# source_A.net
KiCad netlist of a schematic drawn in Altium Designer
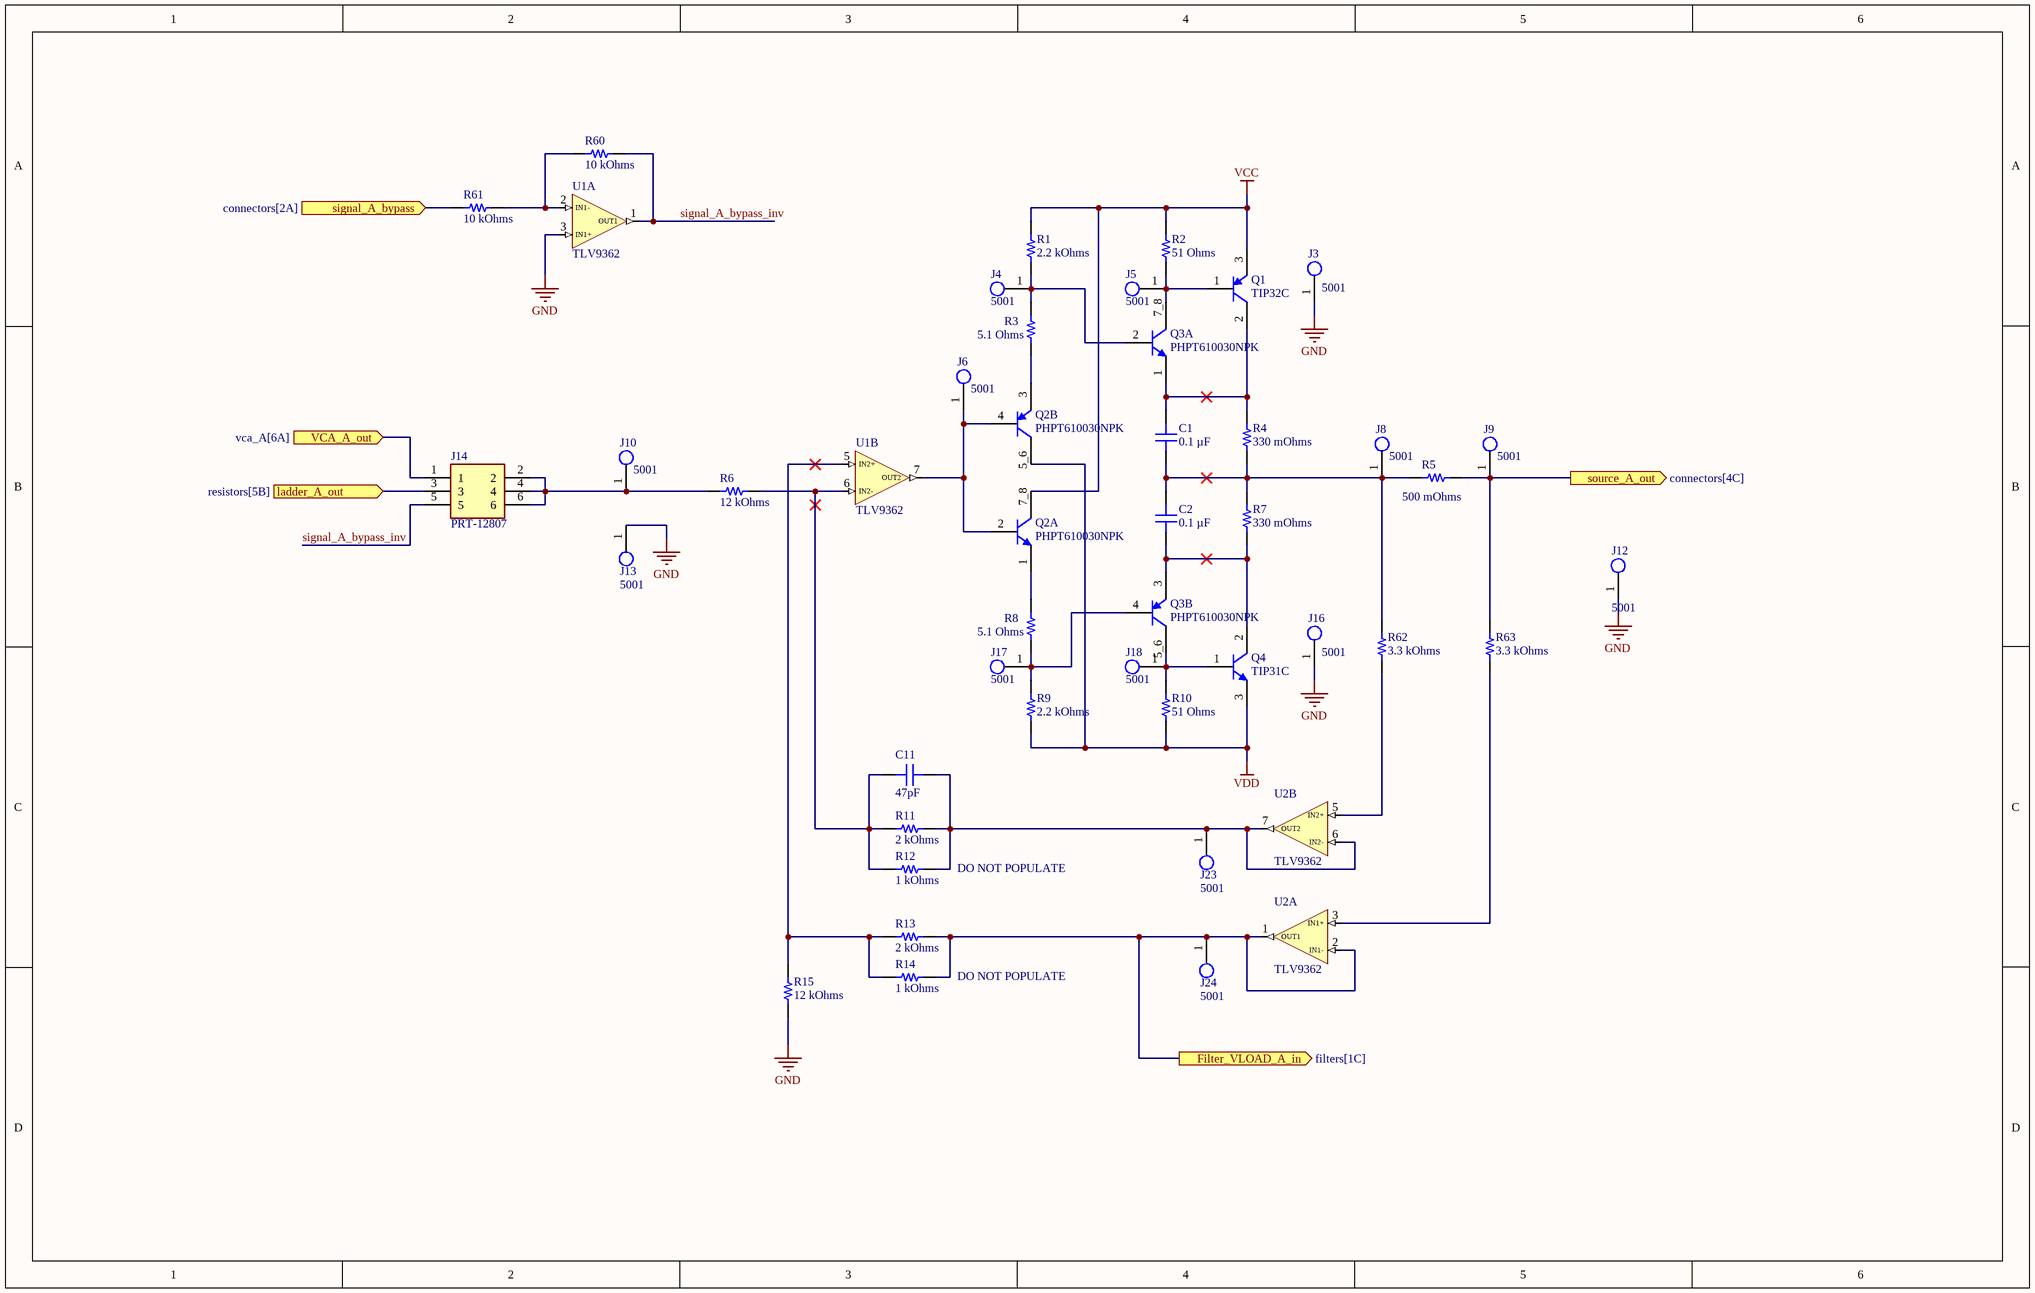
[diagram p0: source_A.SchDoc]

(export (version "E")
  (design (tool "Eeschema 10.0.6"))
  (components
    (comp (ref "C1")
      (value "0.1 µF")
      (footprint "CAP 1206_3216 - 0.8MM")
      (description "CAP CER 0.1UF 50V X7R 1206")
      (fields
        (field (name "PART NUMBER") "885012208087")
        (field (name "CAPACITANCE") "0.1 µF")
        (field (name "MANUFACTURER") "Würth Elektronik")
      )
      (libsource (lib "Celestial Altium Library - altium_library") (part "Capacitor"))
    )
    (comp (ref "C2")
      (value "0.1 µF")
      (footprint "CAP 1206_3216 - 0.8MM")
      (description "CAP CER 0.1UF 50V X7R 1206")
      (fields
        (field (name "PART NUMBER") "885012208087")
        (field (name "CAPACITANCE") "0.1 µF")
        (field (name "MANUFACTURER") "Würth Elektronik")
      )
      (libsource (lib "Celestial Altium Library - altium_library") (part "Capacitor"))
    )
    (comp (ref "C11")
      (value "47pF")
      (footprint "CAP 1206_3216 - 1.8MM")
      (description "CAP CER 47PF 1KV C0G/NP0 1206")
      (fields
        (field (name "PART NUMBER") "1206AA470KAT1A")
        (field (name "CAPACITANCE") "47pF")
        (field (name "MANUFACTURER") "AVX Corporation")
      )
      (libsource (lib "Celestial Altium Library - altium_library") (part "Capacitor"))
    )
    (comp (ref "J3")
      (value "5001")
      (footprint "FP-5001-MFG")
      (description "PC TEST POINT MINIATURE BLACK")
      (libsource (lib "za_koncar") (part "CMP-2000-05181-2"))
    )
    (comp (ref "J4")
      (value "5001")
      (footprint "FP-5001-MFG")
      (description "PC TEST POINT MINIATURE BLACK")
      (libsource (lib "za_koncar") (part "CMP-2000-05181-2"))
    )
    (comp (ref "J5")
      (value "5001")
      (footprint "FP-5001-MFG")
      (description "PC TEST POINT MINIATURE BLACK")
      (libsource (lib "za_koncar") (part "CMP-2000-05181-2"))
    )
    (comp (ref "J6")
      (value "5001")
      (footprint "FP-5001-MFG")
      (description "PC TEST POINT MINIATURE BLACK")
      (libsource (lib "za_koncar") (part "CMP-2000-05181-2"))
    )
    (comp (ref "J8")
      (value "5001")
      (footprint "FP-5001-MFG")
      (description "PC TEST POINT MINIATURE BLACK")
      (libsource (lib "za_koncar") (part "CMP-2000-05181-2"))
    )
    (comp (ref "J9")
      (value "5001")
      (footprint "FP-5001-MFG")
      (description "PC TEST POINT MINIATURE BLACK")
      (libsource (lib "za_koncar") (part "CMP-2000-05181-2"))
    )
    (comp (ref "J10")
      (value "5001")
      (footprint "FP-5001-MFG")
      (description "PC TEST POINT MINIATURE BLACK")
      (libsource (lib "za_koncar") (part "CMP-2000-05181-2"))
    )
    (comp (ref "J12")
      (value "5001")
      (footprint "FP-5001-MFG")
      (description "PC TEST POINT MINIATURE BLACK")
      (libsource (lib "za_koncar") (part "CMP-2000-05181-2"))
    )
    (comp (ref "J13")
      (value "5001")
      (footprint "FP-5001-MFG")
      (description "PC TEST POINT MINIATURE BLACK")
      (libsource (lib "za_koncar") (part "CMP-2000-05181-2"))
    )
    (comp (ref "J14")
      (value "PRT-12807")
      (footprint "HDRV6W82P254_2X3_762X500X884P")
      (description "Connector")
      (fields (field (name "MOUSER PART NUMBER") "474-PRT-12807"))
      (libsource (lib "za_koncar") (part "PRT-12807"))
    )
    (comp (ref "J16")
      (value "5001")
      (footprint "FP-5001-MFG")
      (description "PC TEST POINT MINIATURE BLACK")
      (libsource (lib "za_koncar") (part "CMP-2000-05181-2"))
    )
    (comp (ref "J17")
      (value "5001")
      (footprint "FP-5001-MFG")
      (description "PC TEST POINT MINIATURE BLACK")
      (libsource (lib "za_koncar") (part "CMP-2000-05181-2"))
    )
    (comp (ref "J18")
      (value "5001")
      (footprint "FP-5001-MFG")
      (description "PC TEST POINT MINIATURE BLACK")
      (libsource (lib "za_koncar") (part "CMP-2000-05181-2"))
    )
    (comp (ref "J23")
      (value "5001")
      (footprint "FP-5001-MFG")
      (description "PC TEST POINT MINIATURE BLACK")
      (libsource (lib "za_koncar") (part "CMP-2000-05181-2"))
    )
    (comp (ref "J24")
      (value "5001")
      (footprint "FP-5001-MFG")
      (description "PC TEST POINT MINIATURE BLACK")
      (libsource (lib "za_koncar") (part "CMP-2000-05181-2"))
    )
    (comp (ref "Q1")
      (value "TIP32C")
      (footprint "ONSC-TO-220-3-221A-09")
      (description "Complementary Silicon Plastic Power Transistor, 3-Pin TO-220, Tube")
      (fields (field (name "MANUFACTURER") "On Semiconductor"))
      (libsource (lib "ON Semi General Purpose Transistors") (part "TIP32C"))
    )
    (comp (ref "Q2")
      (value "PHPT610030NPK")
      (footprint "TRANS_BUK9K18-40E,115")
      (libsource (lib "za_koncar") (part "PHPT610030NPK"))
    )
    (comp (ref "Q3")
      (value "PHPT610030NPK")
      (footprint "TRANS_BUK9K18-40E,115")
      (libsource (lib "za_koncar") (part "PHPT610030NPK"))
    )
    (comp (ref "Q4")
      (value "TIP31C")
      (footprint "ONSC-TO-220-3-221A-09")
      (description "Complementary Silicon Plastic Power Transistor, 3-Pin TO-220, Tube")
      (fields (field (name "MANUFACTURER") "On Semiconductor"))
      (libsource (lib "ON Semi General Purpose Transistors") (part "TIP31C"))
    )
    (comp (ref "R1")
      (value "2.2 kOhms")
      (footprint "RES 1206_3216")
      (description "RES SMD 2.2K OHM 5% 1/4W 1206")
      (fields
        (field (name "PART NUMBER") "ERJ-8GEYJ222V")
        (field (name "MANUFACTURER") "Panasonic Electronic Components")
      )
      (libsource (lib "Celestial Altium Library - altium_library") (part "Resistor"))
    )
    (comp (ref "R2")
      (value "51 Ohms")
      (footprint "RES 1206_3216")
      (description "RES SMD 51 OHM 5% 1/4W 1206")
      (fields
        (field (name "PART NUMBER") "ERJ-8GEYJ510V")
        (field (name "MANUFACTURER") "Panasonic Electronic Components")
      )
      (libsource (lib "Celestial Altium Library - altium_library") (part "Resistor"))
    )
    (comp (ref "R3")
      (value "5.1 Ohms")
      (footprint "RES 1206_3216")
      (description "RES SMD 5.1 OHM 5% 1/4W 1206")
      (fields
        (field (name "PART NUMBER") "ERJ-8GEYJ5R1V")
        (field (name "MANUFACTURER") "Panasonic Electronic Components")
      )
      (libsource (lib "Celestial Altium Library - altium_library") (part "Resistor"))
    )
    (comp (ref "R4")
      (value "330 mOhms")
      (footprint "STACKPOLE CSR2512")
      (description "RES 0.33 OHM 1% 2W 2512")
      (fields
        (field (name "PART NUMBER") "CSRN2512FKR330")
        (field (name "MANUFACTURER") "Stackpole Electronics Inc")
      )
      (libsource (lib "Celestial Altium Library - altium_library") (part "Resistor"))
    )
    (comp (ref "R5")
      (value "500 mOhms")
      (footprint "STACKPOLE CSR2512")
      (description "RES 0.5 OHM 1% 2W 2512")
      (fields
        (field (name "PART NUMBER") "CSRN2512FKR500")
        (field (name "MANUFACTURER") "Stackpole Electronics Inc")
      )
      (libsource (lib "Celestial Altium Library - altium_library") (part "Resistor"))
    )
    (comp (ref "R6")
      (value "12 kOhms")
      (footprint "RES 1206_3216")
      (description "RES SMD 12K OHM 0.1% 1/4W 1206")
      (fields
        (field (name "PART NUMBER") "ERA-8AEB123V")
        (field (name "MANUFACTURER") "Panasonic Electronic Components")
      )
      (libsource (lib "Celestial Altium Library - altium_library") (part "Resistor"))
    )
    (comp (ref "R7")
      (value "330 mOhms")
      (footprint "STACKPOLE CSR2512")
      (description "RES 0.33 OHM 1% 2W 2512")
      (fields
        (field (name "PART NUMBER") "CSRN2512FKR330")
        (field (name "MANUFACTURER") "Stackpole Electronics Inc")
      )
      (libsource (lib "Celestial Altium Library - altium_library") (part "Resistor"))
    )
    (comp (ref "R8")
      (value "5.1 Ohms")
      (footprint "RES 1206_3216")
      (description "RES SMD 5.1 OHM 5% 1/4W 1206")
      (fields
        (field (name "PART NUMBER") "ERJ-8GEYJ5R1V")
        (field (name "MANUFACTURER") "Panasonic Electronic Components")
      )
      (libsource (lib "Celestial Altium Library - altium_library") (part "Resistor"))
    )
    (comp (ref "R9")
      (value "2.2 kOhms")
      (footprint "RES 1206_3216")
      (description "RES SMD 2.2K OHM 5% 1/4W 1206")
      (fields
        (field (name "PART NUMBER") "ERJ-8GEYJ222V")
        (field (name "MANUFACTURER") "Panasonic Electronic Components")
      )
      (libsource (lib "Celestial Altium Library - altium_library") (part "Resistor"))
    )
    (comp (ref "R10")
      (value "51 Ohms")
      (footprint "RES 1206_3216")
      (description "RES SMD 51 OHM 5% 1/4W 1206")
      (fields
        (field (name "PART NUMBER") "ERJ-8GEYJ510V")
        (field (name "MANUFACTURER") "Panasonic Electronic Components")
      )
      (libsource (lib "Celestial Altium Library - altium_library") (part "Resistor"))
    )
    (comp (ref "R11")
      (value "2 kOhms")
      (footprint "RES 1206_3216")
      (description "RES SMD 2K OHM 0.1% 1/4W 1206")
      (fields
        (field (name "PART NUMBER") "ERA-8AEB202V")
        (field (name "MANUFACTURER") "Panasonic Electronic Components")
      )
      (libsource (lib "Celestial Altium Library - altium_library") (part "Resistor"))
    )
    (comp (ref "R12")
      (value "1 kOhms")
      (footprint "RES 1206_3216")
      (description "RES SMD 1K OHM 0.1% 1/4W 1206")
      (fields
        (field (name "PART NUMBER") "ERA-8AEB102V")
        (field (name "MANUFACTURER") "Panasonic Electronic Components")
      )
      (libsource (lib "Celestial Altium Library - altium_library") (part "Resistor"))
    )
    (comp (ref "R13")
      (value "2 kOhms")
      (footprint "RES 1206_3216")
      (description "RES SMD 2K OHM 0.1% 1/4W 1206")
      (fields
        (field (name "PART NUMBER") "ERA-8AEB202V")
        (field (name "MANUFACTURER") "Panasonic Electronic Components")
      )
      (libsource (lib "Celestial Altium Library - altium_library") (part "Resistor"))
    )
    (comp (ref "R14")
      (value "1 kOhms")
      (footprint "RES 1206_3216")
      (description "RES SMD 1K OHM 0.1% 1/4W 1206")
      (fields
        (field (name "PART NUMBER") "ERA-8AEB102V")
        (field (name "MANUFACTURER") "Panasonic Electronic Components")
      )
      (libsource (lib "Celestial Altium Library - altium_library") (part "Resistor"))
    )
    (comp (ref "R15")
      (value "12 kOhms")
      (footprint "RES 1206_3216")
      (description "RES SMD 12K OHM 0.1% 1/4W 1206")
      (fields
        (field (name "PART NUMBER") "ERA-8AEB123V")
        (field (name "MANUFACTURER") "Panasonic Electronic Components")
      )
      (libsource (lib "Celestial Altium Library - altium_library") (part "Resistor"))
    )
    (comp (ref "R60")
      (value "10 kOhms")
      (footprint "YAGEO RES 1206_3216")
      (description "RES SMD 10K OHM 1% 1/4W 1206")
      (fields (field (name "PART NUMBER") "RT1206FRE0710KL") (field (name "MANUFACTURER") "Yageo"))
      (libsource (lib "Celestial Altium Library - altium_library") (part "Resistor"))
    )
    (comp (ref "R61")
      (value "10 kOhms")
      (footprint "YAGEO RES 1206_3216")
      (description "RES SMD 10K OHM 1% 1/4W 1206")
      (fields (field (name "PART NUMBER") "RT1206FRE0710KL") (field (name "MANUFACTURER") "Yageo"))
      (libsource (lib "Celestial Altium Library - altium_library") (part "Resistor"))
    )
    (comp (ref "R62")
      (value "3.3 kOhms")
      (footprint "YAGEO RES 1206_3216")
      (description "RES SMD 3.3K OHM 1% 1/4W 1206")
      (fields (field (name "PART NUMBER") "RT1206FRE073K3L") (field (name "MANUFACTURER") "Yageo"))
      (libsource (lib "Celestial Altium Library - altium_library") (part "Resistor"))
    )
    (comp (ref "R63")
      (value "3.3 kOhms")
      (footprint "YAGEO RES 1206_3216")
      (description "RES SMD 3.3K OHM 1% 1/4W 1206")
      (fields (field (name "PART NUMBER") "RT1206FRE073K3L") (field (name "MANUFACTURER") "Yageo"))
      (libsource (lib "Celestial Altium Library - altium_library") (part "Resistor"))
    )
    (comp (ref "U1")
      (value "TLV9362")
      (footprint "za_koncar:SOIC8-127P600X175-8N")
      (description "TLV936x 10-MHz, 40-V, RRO, Operational Amplifie")
      (libsource (lib "za_koncar") (part "TLV9362"))
    )
    (comp (ref "U2")
      (value "TLV9362")
      (footprint "za_koncar:SOIC8-127P600X175-8N")
      (description "TLV936x 10-MHz, 40-V, RRO, Operational Amplifie")
      (libsource (lib "za_koncar") (part "TLV9362"))
    )
  )
  (nets
    (net (code "1") (name "/Filter_VLOAD_A_in") (class "Default")
      (node (ref "J24") (pin "1") (pinfunction "1_1") (pintype "passive"))
      (node (ref "R13") (pin "2") (pinfunction "2_2") (pintype "passive"))
      (node (ref "R14") (pin "2") (pinfunction "2_2") (pintype "passive"))
      (node (ref "U2") (pin "1") (pinfunction "OUT1_1") (pintype "output"))
      (node (ref "U2") (pin "2") (pinfunction "IN1-_2") (pintype "input"))
    )
    (net (code "2") (name "/VCA_A_out") (class "Default")
      (node (ref "J14") (pin "1") (pinfunction "1_1") (pintype "passive"))
    )
    (net (code "3") (name "/ladder_A_out") (class "Default")
      (node (ref "J14") (pin "3") (pinfunction "3_3") (pintype "passive"))
    )
    (net (code "4") (name "/signal_A_bypass") (class "Default")
      (node (ref "R61") (pin "2") (pinfunction "2_2") (pintype "passive"))
    )
    (net (code "5") (name "/signal_A_bypass_inv") (class "Default")
      (node (ref "J14") (pin "5") (pinfunction "5_5") (pintype "passive"))
      (node (ref "R60") (pin "2") (pinfunction "2_2") (pintype "passive"))
      (node (ref "U1") (pin "1") (pinfunction "OUT1_1") (pintype "output"))
    )
    (net (code "6") (name "/source_A_out") (class "Default")
      (node (ref "J9") (pin "1") (pinfunction "1_1") (pintype "passive"))
      (node (ref "R5") (pin "1") (pinfunction "1_1") (pintype "passive"))
      (node (ref "R63") (pin "1") (pinfunction "1_1") (pintype "passive"))
    )
    (net (code "7") (name "GND") (class "Default")
      (node (ref "J12") (pin "1") (pinfunction "1_1") (pintype "passive"))
      (node (ref "J13") (pin "1") (pinfunction "1_1") (pintype "passive"))
      (node (ref "J16") (pin "1") (pinfunction "1_1") (pintype "passive"))
      (node (ref "J3") (pin "1") (pinfunction "1_1") (pintype "passive"))
      (node (ref "R15") (pin "1") (pinfunction "1_1") (pintype "passive"))
      (node (ref "U1") (pin "3") (pinfunction "IN1+_3") (pintype "input"))
    )
    (net (code "8") (name "Net-(C1-Pad1)") (class "Default")
      (node (ref "C1") (pin "1") (pinfunction "1_1") (pintype "passive"))
      (node (ref "C2") (pin "2") (pinfunction "2_2") (pintype "passive"))
      (node (ref "J8") (pin "1") (pinfunction "1_1") (pintype "passive"))
      (node (ref "R4") (pin "1") (pinfunction "1_1") (pintype "passive"))
      (node (ref "R5") (pin "2") (pinfunction "2_2") (pintype "passive"))
      (node (ref "R62") (pin "1") (pinfunction "1_1") (pintype "passive"))
      (node (ref "R7") (pin "2") (pinfunction "2_2") (pintype "passive"))
    )
    (net (code "9") (name "Net-(J10-Pad1)") (class "Default")
      (node (ref "J10") (pin "1") (pinfunction "1_1") (pintype "passive"))
      (node (ref "J14") (pin "2") (pinfunction "2_2") (pintype "passive"))
      (node (ref "J14") (pin "4") (pinfunction "4_4") (pintype "passive"))
      (node (ref "J14") (pin "6") (pinfunction "6_6") (pintype "passive"))
      (node (ref "R6") (pin "2") (pinfunction "2_2") (pintype "passive"))
    )
    (net (code "10") (name "Net-(Q1-B)") (class "Default")
      (node (ref "J5") (pin "1") (pinfunction "1_1") (pintype "passive"))
      (node (ref "Q1") (pin "1") (pinfunction "B_1") (pintype "passive"))
      (node (ref "Q3") (pin "7_8") (pinfunction "C1_7_8") (pintype "passive"))
      (node (ref "R2") (pin "1") (pinfunction "1_1") (pintype "passive"))
    )
    (net (code "11") (name "Net-(Q1-C)") (class "Default")
      (node (ref "C1") (pin "2") (pinfunction "2_2") (pintype "passive"))
      (node (ref "Q1") (pin "2") (pinfunction "C_2") (pintype "passive"))
      (node (ref "Q3") (pin "1") (pinfunction "E1_1") (pintype "passive"))
      (node (ref "R4") (pin "2") (pinfunction "2_2") (pintype "passive"))
    )
    (net (code "12") (name "Net-(Q2A-B1)") (class "Default")
      (node (ref "J6") (pin "1") (pinfunction "1_1") (pintype "passive"))
      (node (ref "Q2") (pin "2") (pinfunction "B1_2") (pintype "passive"))
      (node (ref "Q2") (pin "4") (pinfunction "B2_4") (pintype "passive"))
      (node (ref "U1") (pin "7") (pinfunction "OUT2_7") (pintype "output"))
    )
    (net (code "13") (name "Net-(Q2A-E1)") (class "Default")
      (node (ref "Q2") (pin "1") (pinfunction "E1_1") (pintype "passive"))
      (node (ref "R8") (pin "2") (pinfunction "2_2") (pintype "passive"))
    )
    (net (code "14") (name "Net-(Q2B-E2)") (class "Default")
      (node (ref "Q2") (pin "3") (pinfunction "E2_3") (pintype "passive"))
      (node (ref "R3") (pin "1") (pinfunction "1_1") (pintype "passive"))
    )
    (net (code "15") (name "Net-(Q3A-B1)") (class "Default")
      (node (ref "J4") (pin "1") (pinfunction "1_1") (pintype "passive"))
      (node (ref "Q3") (pin "2") (pinfunction "B1_2") (pintype "passive"))
      (node (ref "R1") (pin "1") (pinfunction "1_1") (pintype "passive"))
      (node (ref "R3") (pin "2") (pinfunction "2_2") (pintype "passive"))
    )
    (net (code "16") (name "Net-(Q3B-B2)") (class "Default")
      (node (ref "J17") (pin "1") (pinfunction "1_1") (pintype "passive"))
      (node (ref "Q3") (pin "4") (pinfunction "B2_4") (pintype "passive"))
      (node (ref "R8") (pin "1") (pinfunction "1_1") (pintype "passive"))
      (node (ref "R9") (pin "2") (pinfunction "2_2") (pintype "passive"))
    )
    (net (code "17") (name "Net-(Q3B-C2)") (class "Default")
      (node (ref "J18") (pin "1") (pinfunction "1_1") (pintype "passive"))
      (node (ref "Q3") (pin "5_6") (pinfunction "C2_5_6") (pintype "passive"))
      (node (ref "Q4") (pin "1") (pinfunction "B_1") (pintype "passive"))
      (node (ref "R10") (pin "2") (pinfunction "2_2") (pintype "passive"))
    )
    (net (code "18") (name "Net-(Q3B-E2)") (class "Default")
      (node (ref "C2") (pin "1") (pinfunction "1_1") (pintype "passive"))
      (node (ref "Q3") (pin "3") (pinfunction "E2_3") (pintype "passive"))
      (node (ref "Q4") (pin "2") (pinfunction "C_2") (pintype "passive"))
      (node (ref "R7") (pin "1") (pinfunction "1_1") (pintype "passive"))
    )
    (net (code "19") (name "Net-(U1A-IN1-)") (class "Default")
      (node (ref "R60") (pin "1") (pinfunction "1_1") (pintype "passive"))
      (node (ref "R61") (pin "1") (pinfunction "1_1") (pintype "passive"))
      (node (ref "U1") (pin "2") (pinfunction "IN1-_2") (pintype "input"))
    )
    (net (code "20") (name "Net-(U1B-IN2+)") (class "Default")
      (node (ref "R13") (pin "1") (pinfunction "1_1") (pintype "passive"))
      (node (ref "R14") (pin "1") (pinfunction "1_1") (pintype "passive"))
      (node (ref "R15") (pin "2") (pinfunction "2_2") (pintype "passive"))
      (node (ref "U1") (pin "5") (pinfunction "IN2+_5") (pintype "input"))
    )
    (net (code "21") (name "Net-(U1B-IN2-)") (class "Default")
      (node (ref "C11") (pin "1") (pinfunction "1_1") (pintype "passive"))
      (node (ref "R11") (pin "1") (pinfunction "1_1") (pintype "passive"))
      (node (ref "R12") (pin "1") (pinfunction "1_1") (pintype "passive"))
      (node (ref "R6") (pin "1") (pinfunction "1_1") (pintype "passive"))
      (node (ref "U1") (pin "6") (pinfunction "IN2-_6") (pintype "input"))
    )
    (net (code "22") (name "Net-(U2A-IN1+)") (class "Default")
      (node (ref "R63") (pin "2") (pinfunction "2_2") (pintype "passive"))
      (node (ref "U2") (pin "3") (pinfunction "IN1+_3") (pintype "input"))
    )
    (net (code "23") (name "Net-(U2B-IN2+)") (class "Default")
      (node (ref "R62") (pin "2") (pinfunction "2_2") (pintype "passive"))
      (node (ref "U2") (pin "5") (pinfunction "IN2+_5") (pintype "input"))
    )
    (net (code "24") (name "Net-(U2B-IN2-)") (class "Default")
      (node (ref "C11") (pin "2") (pinfunction "2_2") (pintype "passive"))
      (node (ref "J23") (pin "1") (pinfunction "1_1") (pintype "passive"))
      (node (ref "R11") (pin "2") (pinfunction "2_2") (pintype "passive"))
      (node (ref "R12") (pin "2") (pinfunction "2_2") (pintype "passive"))
      (node (ref "U2") (pin "6") (pinfunction "IN2-_6") (pintype "input"))
      (node (ref "U2") (pin "7") (pinfunction "OUT2_7") (pintype "output"))
    )
    (net (code "25") (name "VCC") (class "Default")
      (node (ref "Q1") (pin "3") (pinfunction "E_3") (pintype "passive"))
      (node (ref "Q2") (pin "7_8") (pinfunction "C1_7_8") (pintype "passive"))
      (node (ref "R1") (pin "2") (pinfunction "2_2") (pintype "passive"))
      (node (ref "R2") (pin "2") (pinfunction "2_2") (pintype "passive"))
    )
    (net (code "26") (name "VDD") (class "Default")
      (node (ref "Q2") (pin "5_6") (pinfunction "C2_5_6") (pintype "passive"))
      (node (ref "Q4") (pin "3") (pinfunction "E_3") (pintype "passive"))
      (node (ref "R10") (pin "1") (pinfunction "1_1") (pintype "passive"))
      (node (ref "R9") (pin "1") (pinfunction "1_1") (pintype "passive"))
    )
  )
)
